# Line_Follower.net
KiCad netlist of a schematic drawn in EAGLE
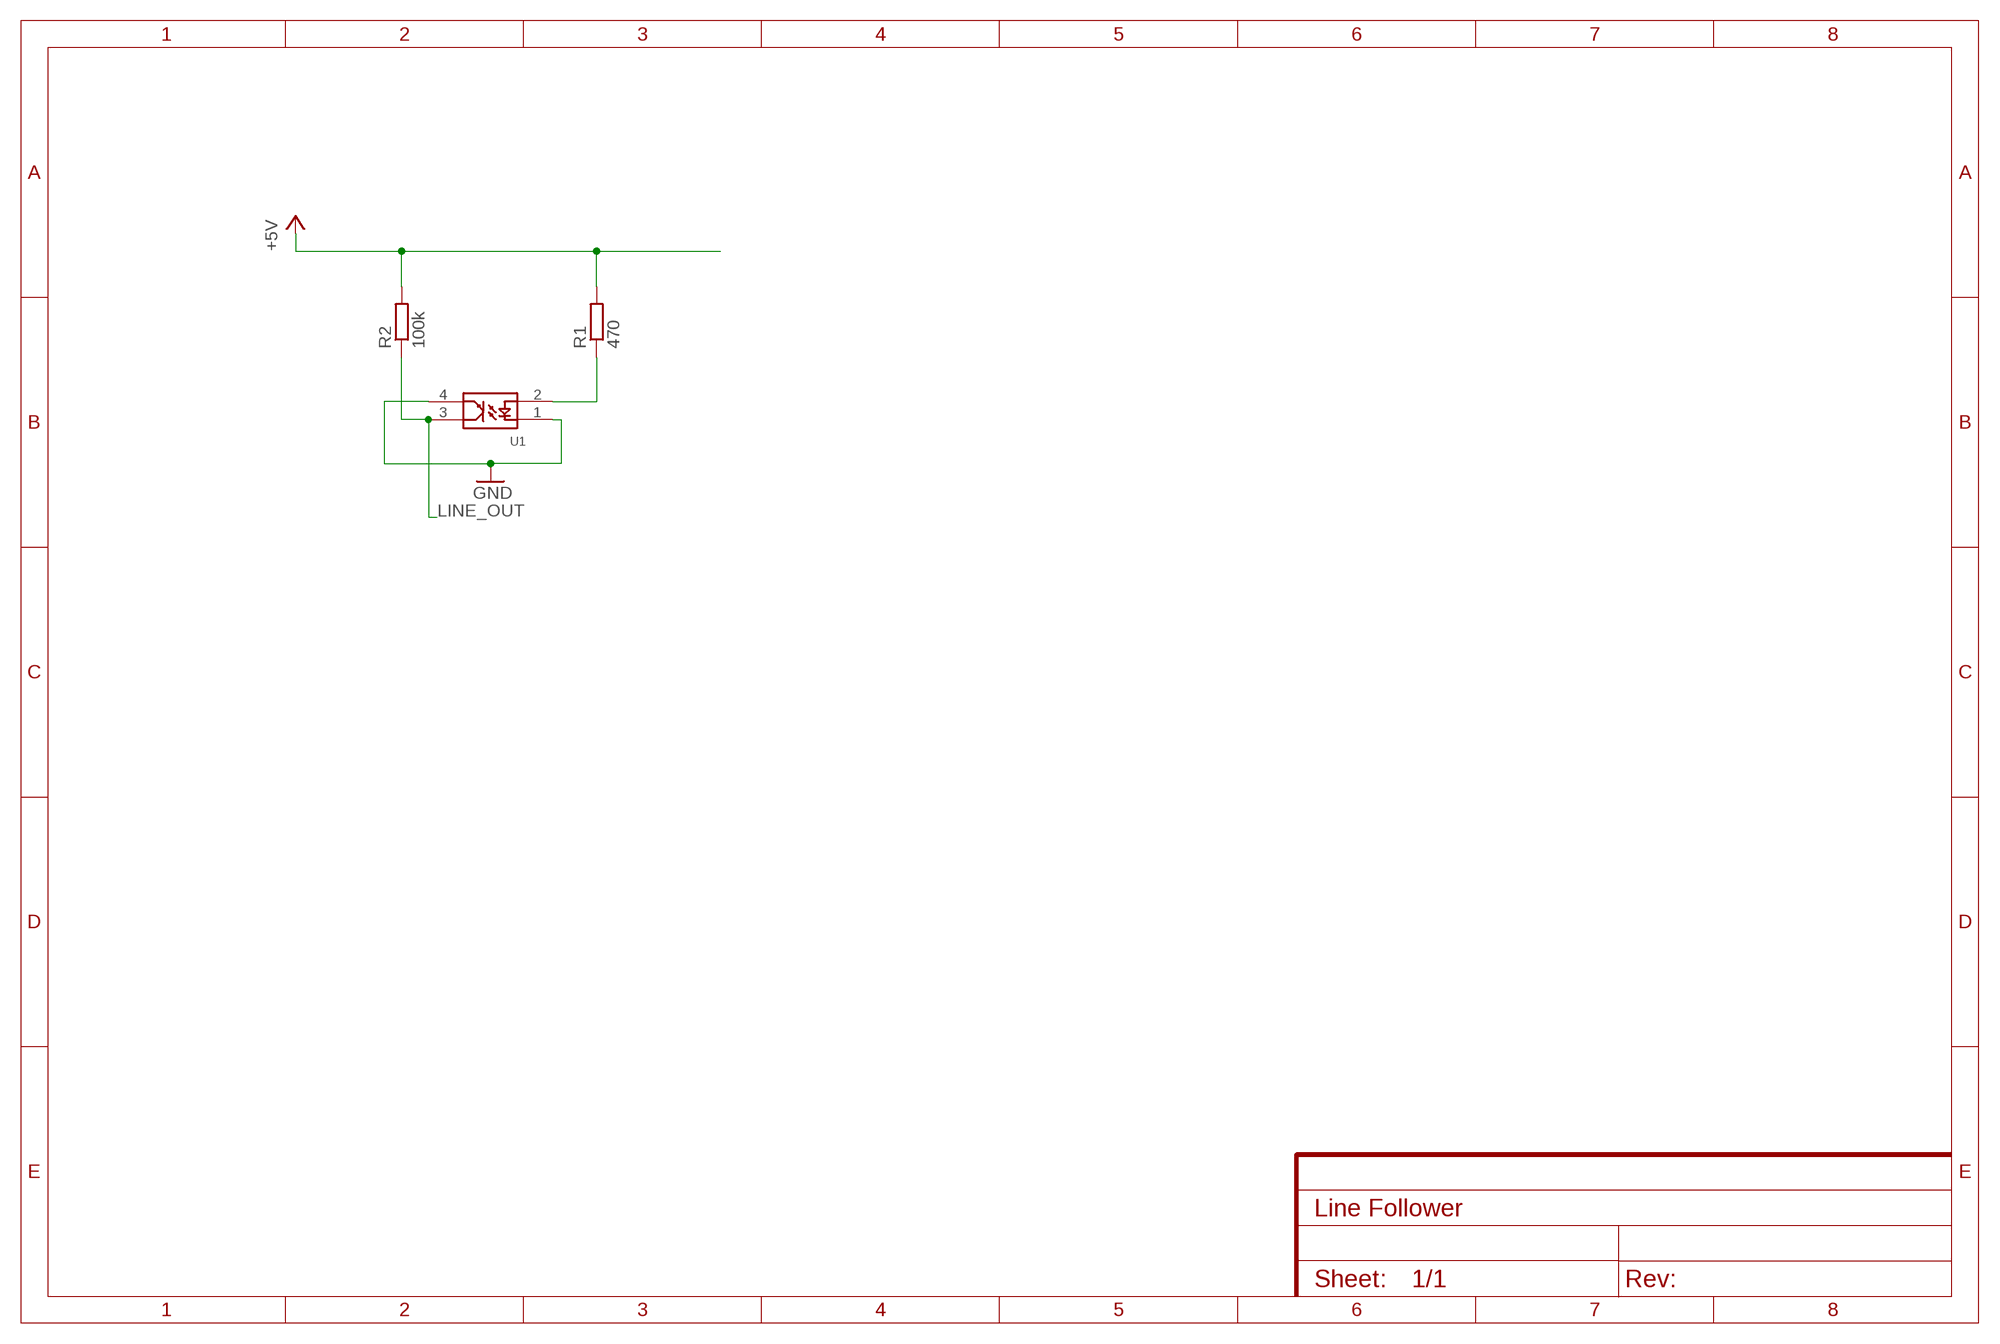
[diagram p0: schematic, sheet 1]

(export (version "E")
  (design (tool "Eeschema 10.0.6"))
  (components
    (comp (ref "R1")
      (value "470")
      (footprint "eagle-import:0204_7")
      (libsource (lib "eagle-import") (part "R-EU_0204/7"))
    )
    (comp (ref "R2")
      (value "100k")
      (footprint "eagle-import:0204_7")
      (libsource (lib "eagle-import") (part "R-EU_0204/7"))
    )
    (comp (ref "U1")
      (value "OPB704")
      (footprint "eagle-import:22-23-2041")
      (libsource (lib "eagle-import") (part "OPB704"))
    )
  )
  (nets
    (net (code "1") (name "+5V") (class "Default")
      (node (ref "R1") (pin "2") (pinfunction "2_2") (pintype "passive"))
      (node (ref "R2") (pin "2") (pinfunction "2_2") (pintype "passive"))
    )
    (net (code "2") (name "/LINE_OUT") (class "Default")
      (node (ref "R2") (pin "1") (pinfunction "1_1") (pintype "passive"))
      (node (ref "U1") (pin "3") (pinfunction "3_3") (pintype "bidirectional"))
    )
    (net (code "3") (name "GND") (class "Default")
      (node (ref "U1") (pin "1") (pinfunction "1_1") (pintype "bidirectional"))
      (node (ref "U1") (pin "4") (pinfunction "4_4") (pintype "bidirectional"))
    )
    (net (code "4") (name "Net-(R1-Pad1)") (class "Default")
      (node (ref "R1") (pin "1") (pinfunction "1_1") (pintype "passive"))
      (node (ref "U1") (pin "2") (pinfunction "2_2") (pintype "bidirectional"))
    )
  )
)
